# ProtoHu_revA_layer1.net
KiCad netlist of a schematic drawn in EAGLE
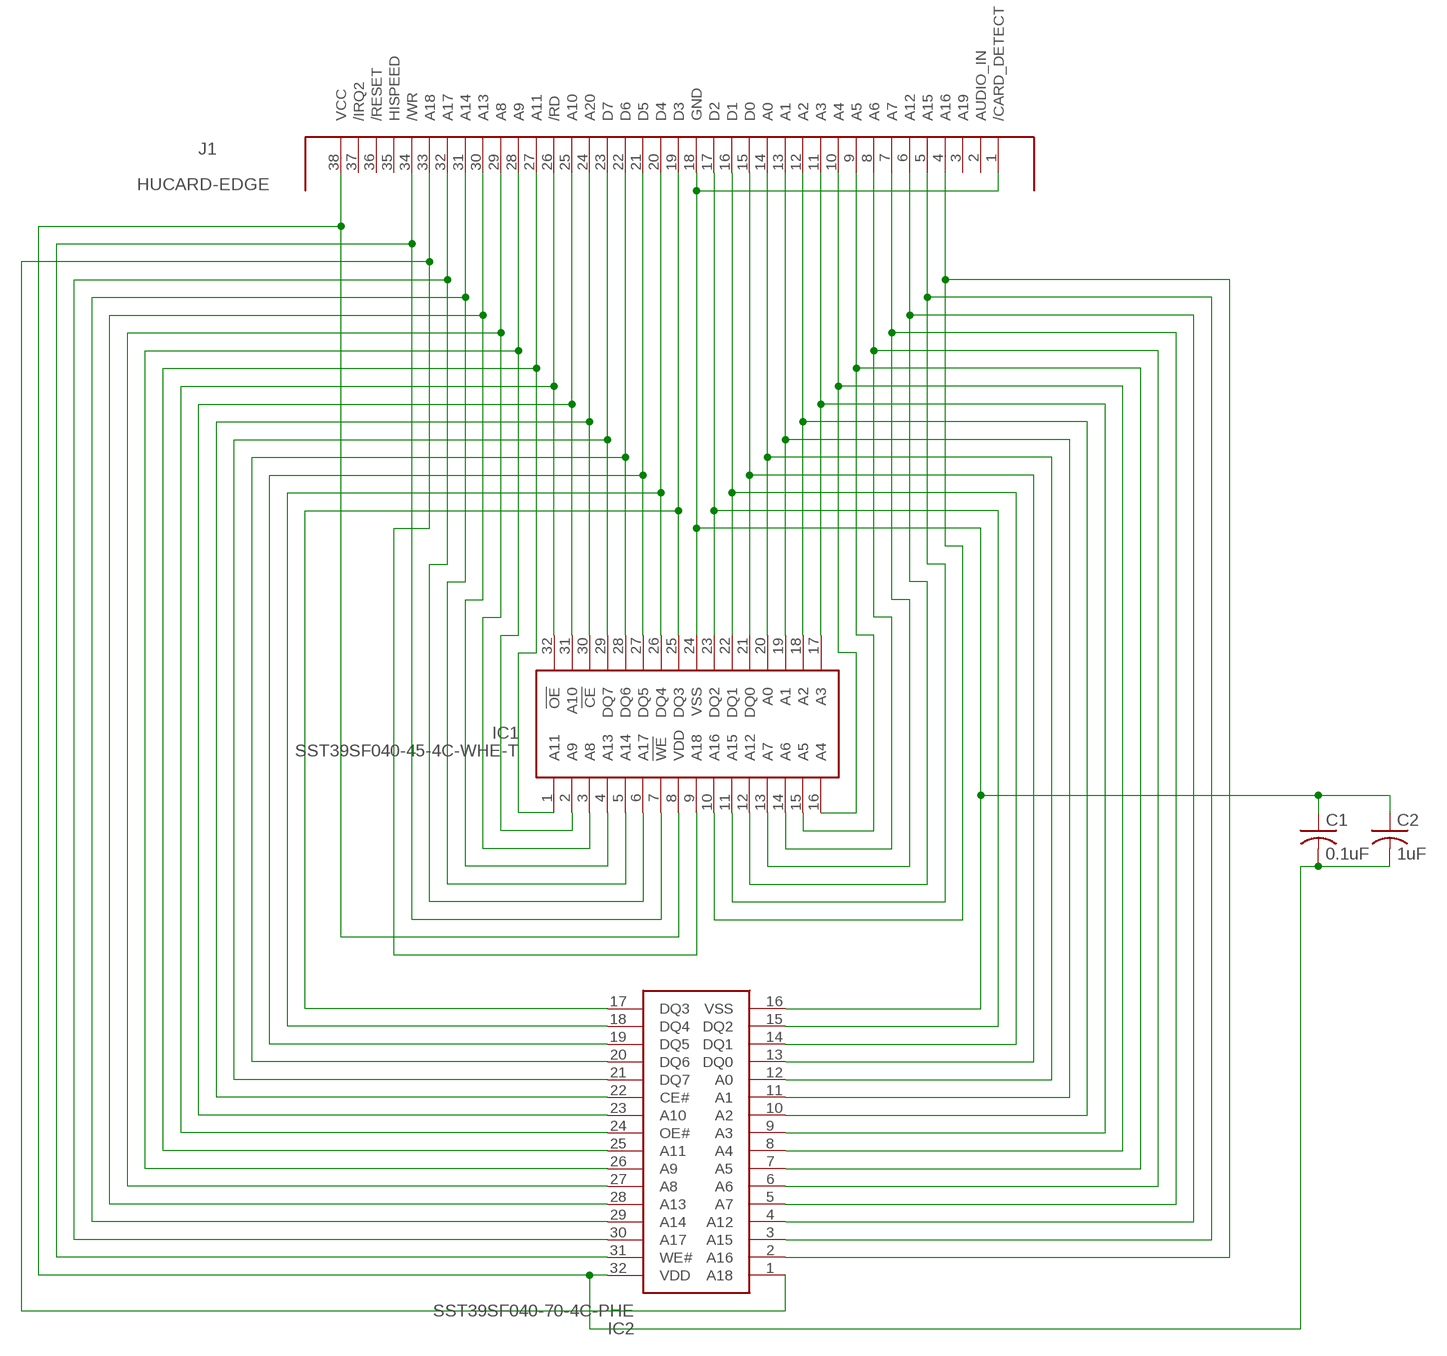
[diagram p0: schematic, sheet 1]

(export (version "E")
  (design (tool "Eeschema 10.0.6"))
  (components
    (comp (ref "C1")
      (value "0.1uF")
      (footprint "eagle-import:C0603")
      (libsource (lib "eagle-import") (part "C-USC0603"))
    )
    (comp (ref "C2")
      (value "1uF")
      (footprint "eagle-import:C0603")
      (libsource (lib "eagle-import") (part "C-USC0603"))
    )
    (comp (ref "IC1")
      (value "SST39SF040-45-4C-WHE-T")
      (footprint "eagle-import:SOP50P1400X120-32N")
      (fields (field (name "MOUSER_PART_NUMBER") "579-39SF0404CWHET"))
      (libsource (lib "eagle-import") (part "SST39SF040-45-4C-WHE-T"))
    )
    (comp (ref "IC2")
      (value "SST39SF040-70-4C-PHE")
      (footprint "eagle-import:DIP1556W56P254L4191H508Q32N")
      (fields
        (field (name "MOUSER_PART_NUMBER") "804-39SF0407CPHE")
        (field (name "RS_PART_NUMBER") "8104037P")
      )
      (libsource (lib "eagle-import") (part "SST39SF040-70-4C-PHE"))
    )
    (comp (ref "J1")
      (value "HUCARD-EDGE")
      (footprint "eagle-import:HUCARD-EDGE")
      (libsource (lib "eagle-import") (part "HUCARD-EDGE"))
    )
  )
  (nets
    (net (code "1") (name "Net-(IC1-A0)") (class "Default")
      (node (ref "IC1") (pin "20") (pinfunction "A0_20") (pintype "input"))
      (node (ref "IC2") (pin "12") (pinfunction "A0_12") (pintype "bidirectional"))
      (node (ref "J1") (pin "14") (pinfunction "A0_14") (pintype "output"))
    )
    (net (code "2") (name "Net-(IC1-A1)") (class "Default")
      (node (ref "IC1") (pin "19") (pinfunction "A1_19") (pintype "input"))
      (node (ref "IC2") (pin "11") (pinfunction "A1_11") (pintype "bidirectional"))
      (node (ref "J1") (pin "13") (pinfunction "A1_13") (pintype "output"))
    )
    (net (code "3") (name "Net-(IC1-A2)") (class "Default")
      (node (ref "IC1") (pin "18") (pinfunction "A2_18") (pintype "input"))
      (node (ref "IC2") (pin "10") (pinfunction "A2_10") (pintype "bidirectional"))
      (node (ref "J1") (pin "12") (pinfunction "A2_12") (pintype "output"))
    )
    (net (code "4") (name "Net-(IC1-A3)") (class "Default")
      (node (ref "IC1") (pin "17") (pinfunction "A3_17") (pintype "input"))
      (node (ref "IC2") (pin "9") (pinfunction "A3_9") (pintype "bidirectional"))
      (node (ref "J1") (pin "11") (pinfunction "A3_11") (pintype "output"))
    )
    (net (code "5") (name "Net-(IC1-A4)") (class "Default")
      (node (ref "IC1") (pin "16") (pinfunction "A4_16") (pintype "input"))
      (node (ref "IC2") (pin "8") (pinfunction "A4_8") (pintype "bidirectional"))
      (node (ref "J1") (pin "10") (pinfunction "A4_10") (pintype "output"))
    )
    (net (code "6") (name "Net-(IC1-A5)") (class "Default")
      (node (ref "IC1") (pin "15") (pinfunction "A5_15") (pintype "input"))
      (node (ref "IC2") (pin "7") (pinfunction "A5_7") (pintype "bidirectional"))
      (node (ref "J1") (pin "9") (pinfunction "A5_9") (pintype "output"))
    )
    (net (code "7") (name "Net-(IC1-A6)") (class "Default")
      (node (ref "IC1") (pin "14") (pinfunction "A6_14") (pintype "input"))
      (node (ref "IC2") (pin "6") (pinfunction "A6_6") (pintype "bidirectional"))
      (node (ref "J1") (pin "8") (pinfunction "A6_8") (pintype "output"))
    )
    (net (code "8") (name "Net-(IC1-A7)") (class "Default")
      (node (ref "IC1") (pin "13") (pinfunction "A7_13") (pintype "input"))
      (node (ref "IC2") (pin "5") (pinfunction "A7_5") (pintype "bidirectional"))
      (node (ref "J1") (pin "7") (pinfunction "A7_7") (pintype "output"))
    )
    (net (code "9") (name "Net-(IC1-A8)") (class "Default")
      (node (ref "IC1") (pin "3") (pinfunction "A8_3") (pintype "input"))
      (node (ref "IC2") (pin "27") (pinfunction "A8_27") (pintype "bidirectional"))
      (node (ref "J1") (pin "29") (pinfunction "A8_29") (pintype "output"))
    )
    (net (code "10") (name "Net-(IC1-A9)") (class "Default")
      (node (ref "IC1") (pin "2") (pinfunction "A9_2") (pintype "input"))
      (node (ref "IC2") (pin "26") (pinfunction "A9_26") (pintype "bidirectional"))
      (node (ref "J1") (pin "28") (pinfunction "A9_28") (pintype "output"))
    )
    (net (code "11") (name "Net-(IC1-A10)") (class "Default")
      (node (ref "IC1") (pin "31") (pinfunction "A10_31") (pintype "input"))
      (node (ref "IC2") (pin "23") (pinfunction "A10_23") (pintype "bidirectional"))
      (node (ref "J1") (pin "25") (pinfunction "A10_25") (pintype "output"))
    )
    (net (code "12") (name "Net-(IC1-A11)") (class "Default")
      (node (ref "IC1") (pin "1") (pinfunction "A11_1") (pintype "input"))
      (node (ref "IC2") (pin "25") (pinfunction "A11_25") (pintype "bidirectional"))
      (node (ref "J1") (pin "27") (pinfunction "A11_27") (pintype "output"))
    )
    (net (code "13") (name "Net-(IC1-A12)") (class "Default")
      (node (ref "IC1") (pin "12") (pinfunction "A12_12") (pintype "input"))
      (node (ref "IC2") (pin "4") (pinfunction "A12_4") (pintype "bidirectional"))
      (node (ref "J1") (pin "6") (pinfunction "A12_6") (pintype "output"))
    )
    (net (code "14") (name "Net-(IC1-A13)") (class "Default")
      (node (ref "IC1") (pin "4") (pinfunction "A13_4") (pintype "input"))
      (node (ref "IC2") (pin "28") (pinfunction "A13_28") (pintype "bidirectional"))
      (node (ref "J1") (pin "30") (pinfunction "A13_30") (pintype "output"))
    )
    (net (code "15") (name "Net-(IC1-A14)") (class "Default")
      (node (ref "IC1") (pin "5") (pinfunction "A14_5") (pintype "input"))
      (node (ref "IC2") (pin "29") (pinfunction "A14_29") (pintype "bidirectional"))
      (node (ref "J1") (pin "31") (pinfunction "A14_31") (pintype "output"))
    )
    (net (code "16") (name "Net-(IC1-A15)") (class "Default")
      (node (ref "IC1") (pin "11") (pinfunction "A15_11") (pintype "input"))
      (node (ref "IC2") (pin "3") (pinfunction "A15_3") (pintype "bidirectional"))
      (node (ref "J1") (pin "5") (pinfunction "A15_5") (pintype "output"))
    )
    (net (code "17") (name "Net-(IC1-A16)") (class "Default")
      (node (ref "IC1") (pin "10") (pinfunction "A16_10") (pintype "input"))
      (node (ref "IC2") (pin "2") (pinfunction "A16_2") (pintype "bidirectional"))
      (node (ref "J1") (pin "4") (pinfunction "A16_4") (pintype "output"))
    )
    (net (code "18") (name "Net-(IC1-A17)") (class "Default")
      (node (ref "IC1") (pin "6") (pinfunction "A17_6") (pintype "input"))
      (node (ref "IC2") (pin "30") (pinfunction "A17_30") (pintype "bidirectional"))
      (node (ref "J1") (pin "32") (pinfunction "A17_32") (pintype "output"))
    )
    (net (code "19") (name "Net-(IC1-A18)") (class "Default")
      (node (ref "IC1") (pin "9") (pinfunction "A18_9") (pintype "input"))
      (node (ref "IC2") (pin "1") (pinfunction "A18_1") (pintype "bidirectional"))
      (node (ref "J1") (pin "33") (pinfunction "A18_33") (pintype "output"))
    )
    (net (code "20") (name "Net-(IC1-DQ0)") (class "Default")
      (node (ref "IC1") (pin "21") (pinfunction "DQ0_21") (pintype "bidirectional"))
      (node (ref "IC2") (pin "13") (pinfunction "DQ0_13") (pintype "bidirectional"))
      (node (ref "J1") (pin "15") (pinfunction "D0_15") (pintype "bidirectional"))
    )
    (net (code "21") (name "Net-(IC1-DQ1)") (class "Default")
      (node (ref "IC1") (pin "22") (pinfunction "DQ1_22") (pintype "bidirectional"))
      (node (ref "IC2") (pin "14") (pinfunction "DQ1_14") (pintype "bidirectional"))
      (node (ref "J1") (pin "16") (pinfunction "D1_16") (pintype "bidirectional"))
    )
    (net (code "22") (name "Net-(IC1-DQ2)") (class "Default")
      (node (ref "IC1") (pin "23") (pinfunction "DQ2_23") (pintype "bidirectional"))
      (node (ref "IC2") (pin "15") (pinfunction "DQ2_15") (pintype "bidirectional"))
      (node (ref "J1") (pin "17") (pinfunction "D2_17") (pintype "bidirectional"))
    )
    (net (code "23") (name "Net-(IC1-DQ3)") (class "Default")
      (node (ref "IC1") (pin "25") (pinfunction "DQ3_25") (pintype "bidirectional"))
      (node (ref "IC2") (pin "17") (pinfunction "DQ3_17") (pintype "bidirectional"))
      (node (ref "J1") (pin "19") (pinfunction "D3_19") (pintype "bidirectional"))
    )
    (net (code "24") (name "Net-(IC1-DQ4)") (class "Default")
      (node (ref "IC1") (pin "26") (pinfunction "DQ4_26") (pintype "bidirectional"))
      (node (ref "IC2") (pin "18") (pinfunction "DQ4_18") (pintype "bidirectional"))
      (node (ref "J1") (pin "20") (pinfunction "D4_20") (pintype "bidirectional"))
    )
    (net (code "25") (name "Net-(IC1-DQ5)") (class "Default")
      (node (ref "IC1") (pin "27") (pinfunction "DQ5_27") (pintype "bidirectional"))
      (node (ref "IC2") (pin "19") (pinfunction "DQ5_19") (pintype "bidirectional"))
      (node (ref "J1") (pin "21") (pinfunction "D5_21") (pintype "bidirectional"))
    )
    (net (code "26") (name "Net-(IC1-DQ6)") (class "Default")
      (node (ref "IC1") (pin "28") (pinfunction "DQ6_28") (pintype "bidirectional"))
      (node (ref "IC2") (pin "20") (pinfunction "DQ6_20") (pintype "bidirectional"))
      (node (ref "J1") (pin "22") (pinfunction "D6_22") (pintype "bidirectional"))
    )
    (net (code "27") (name "Net-(IC1-DQ7)") (class "Default")
      (node (ref "IC1") (pin "29") (pinfunction "DQ7_29") (pintype "bidirectional"))
      (node (ref "IC2") (pin "21") (pinfunction "DQ7_21") (pintype "bidirectional"))
      (node (ref "J1") (pin "23") (pinfunction "D7_23") (pintype "bidirectional"))
    )
    (net (code "28") (name "Net-(IC1-VDD)") (class "Default")
      (node (ref "C1") (pin "2") (pinfunction "2_2") (pintype "passive"))
      (node (ref "C2") (pin "2") (pinfunction "2_2") (pintype "passive"))
      (node (ref "IC1") (pin "8") (pinfunction "VDD_8") (pintype "power_in"))
      (node (ref "IC2") (pin "32") (pinfunction "VDD_32") (pintype "bidirectional"))
      (node (ref "J1") (pin "38") (pinfunction "VCC_38") (pintype "power_in"))
    )
    (net (code "29") (name "Net-(IC1-VSS)") (class "Default")
      (node (ref "C1") (pin "1") (pinfunction "1_1") (pintype "passive"))
      (node (ref "C2") (pin "1") (pinfunction "1_1") (pintype "passive"))
      (node (ref "IC1") (pin "24") (pinfunction "VSS_24") (pintype "power_in"))
      (node (ref "IC2") (pin "16") (pinfunction "VSS_16") (pintype "bidirectional"))
      (node (ref "J1") (pin "1") (pinfunction "/CARD_DETECT_1") (pintype "input"))
      (node (ref "J1") (pin "18") (pinfunction "GND_18") (pintype "power_in"))
    )
    (net (code "30") (name "Net-(IC1-~{CE})") (class "Default")
      (node (ref "IC1") (pin "30") (pinfunction "~{CE}_30") (pintype "input"))
      (node (ref "IC2") (pin "22") (pinfunction "CE#_22") (pintype "bidirectional"))
      (node (ref "J1") (pin "24") (pinfunction "A20_24") (pintype "output"))
    )
    (net (code "31") (name "Net-(IC1-~{OE})") (class "Default")
      (node (ref "IC1") (pin "32") (pinfunction "~{OE}_32") (pintype "input"))
      (node (ref "IC2") (pin "24") (pinfunction "OE#_24") (pintype "bidirectional"))
      (node (ref "J1") (pin "26") (pinfunction "/RD_26") (pintype "output"))
    )
    (net (code "32") (name "Net-(IC1-~{WE})") (class "Default")
      (node (ref "IC1") (pin "7") (pinfunction "~{WE}_7") (pintype "input"))
      (node (ref "IC2") (pin "31") (pinfunction "WE#_31") (pintype "bidirectional"))
      (node (ref "J1") (pin "34") (pinfunction "/WR_34") (pintype "output"))
    )
    (net (code "33") (name "unconnected-(J1-A19-Pad3)") (class "Default")
      (node (ref "J1") (pin "3") (pinfunction "A19_3") (pintype "output"))
    )
    (net (code "34") (name "unconnected-(J1-AUDIO_IN-Pad2)") (class "Default")
      (node (ref "J1") (pin "2") (pinfunction "AUDIO_IN_2") (pintype "input"))
    )
    (net (code "35") (name "unconnected-(J1-HISPEED-Pad35)") (class "Default")
      (node (ref "J1") (pin "35") (pinfunction "HISPEED_35") (pintype "output"))
    )
    (net (code "36") (name "unconnected-(J1-{slash}IRQ2-Pad37)") (class "Default")
      (node (ref "J1") (pin "37") (pinfunction "/IRQ2_37") (pintype "bidirectional"))
    )
    (net (code "37") (name "unconnected-(J1-{slash}RESET-Pad36)") (class "Default")
      (node (ref "J1") (pin "36") (pinfunction "/RESET_36") (pintype "bidirectional"))
    )
  )
)
